# USB_Hub.net
KiCad netlist of a schematic drawn in Altium Designer
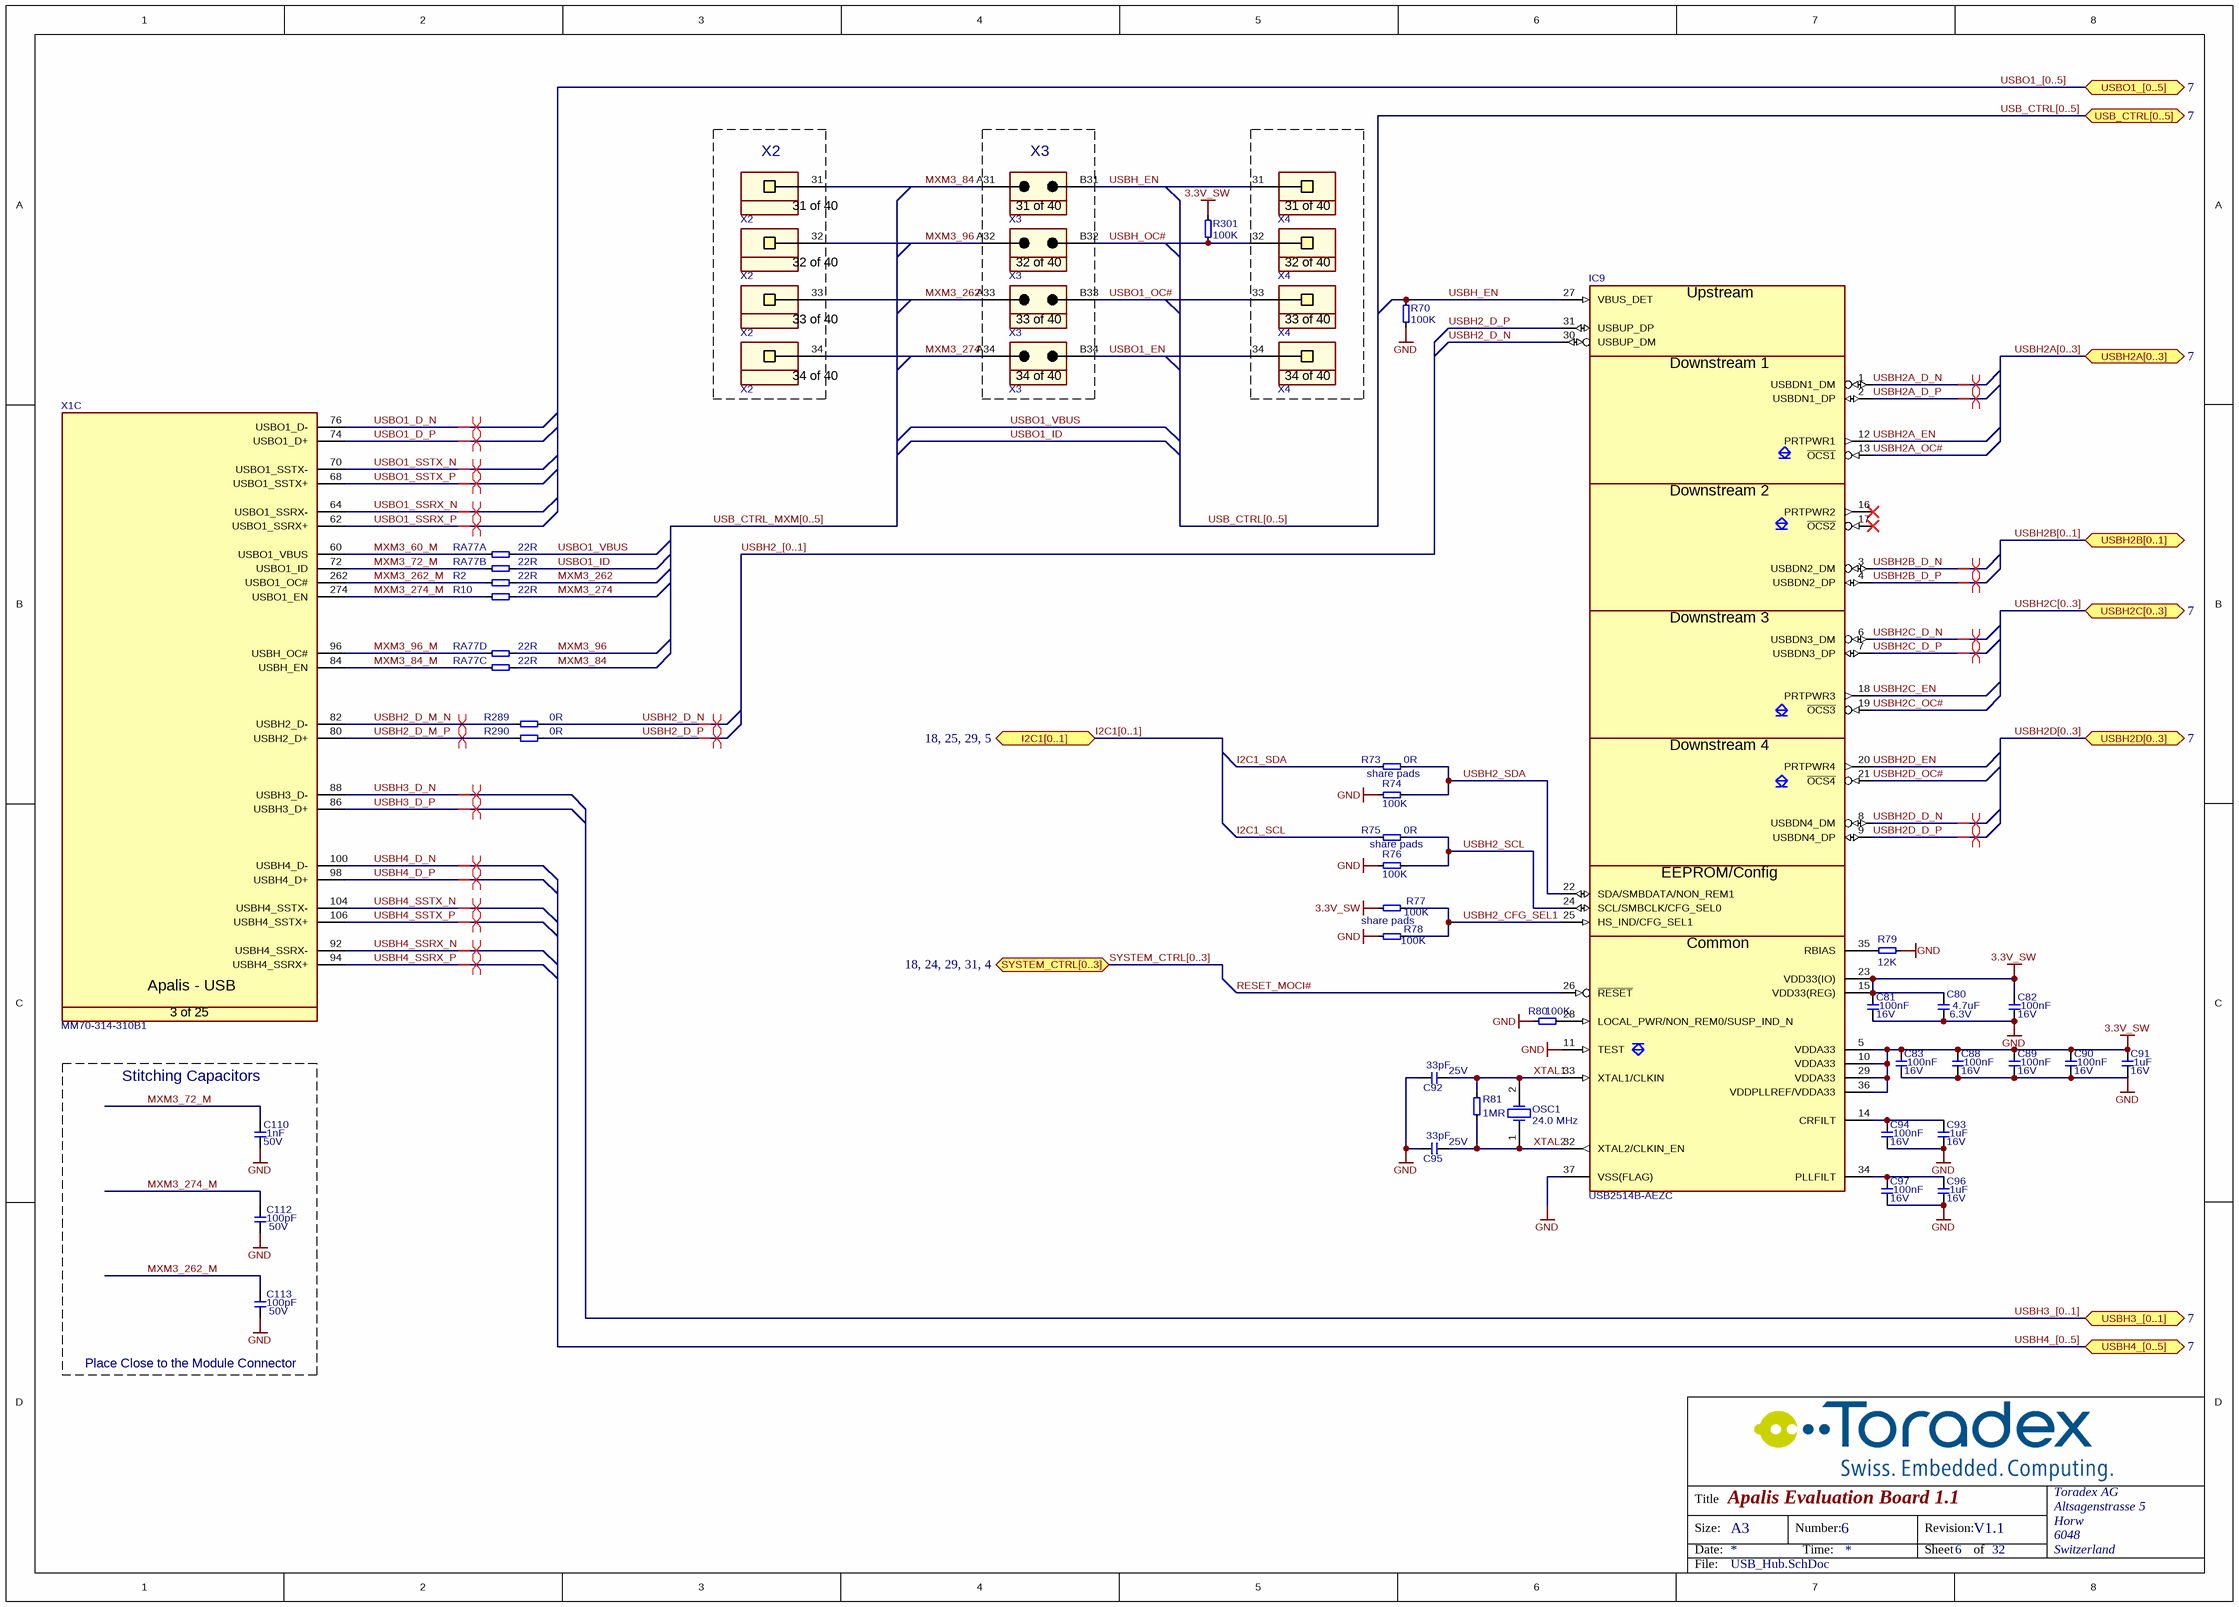
[diagram p0: USB_Hub.SchDoc]

(export (version "E")
  (design (tool "Eeschema 10.0.6"))
  (components
    (comp (ref "C80")
      (value "4.7uF")
      (footprint "T_CAPC0603X33N")
      (description "Capacitor Ceramic X5R 4.7uF 6.3V 20% 0603")
      (fields (field (name "TOLERANCE") "20%") (field (name "RATING") "6.3V"))
      (libsource (lib "Apalis Evaluation Board") (part "C-X5R-4.7uF-6.3V-20%-0603"))
    )
    (comp (ref "C81")
      (value "100nF")
      (footprint "T_CAPC0603X33N")
      (description "Capacitor Ceramic X7R 100nF 16V 10% 0603")
      (fields (field (name "TOLERANCE") "10%") (field (name "RATING") "16V"))
      (libsource (lib "Apalis Evaluation Board") (part "C-X7R-100nF-16V-10%-0603"))
    )
    (comp (ref "C82")
      (value "100nF")
      (footprint "T_CAPC0603X33N")
      (description "Capacitor Ceramic X7R 100nF 16V 10% 0603")
      (fields (field (name "TOLERANCE") "10%") (field (name "RATING") "16V"))
      (libsource (lib "Apalis Evaluation Board") (part "C-X7R-100nF-16V-10%-0603"))
    )
    (comp (ref "C83")
      (value "100nF")
      (footprint "T_CAPC0603X33N")
      (description "Capacitor Ceramic X7R 100nF 16V 10% 0603")
      (fields (field (name "TOLERANCE") "10%") (field (name "RATING") "16V"))
      (libsource (lib "Apalis Evaluation Board") (part "C-X7R-100nF-16V-10%-0603"))
    )
    (comp (ref "C88")
      (value "100nF")
      (footprint "T_CAPC0603X33N")
      (description "Capacitor Ceramic X7R 100nF 16V 10% 0603")
      (fields (field (name "TOLERANCE") "10%") (field (name "RATING") "16V"))
      (libsource (lib "Apalis Evaluation Board") (part "C-X7R-100nF-16V-10%-0603"))
    )
    (comp (ref "C89")
      (value "100nF")
      (footprint "T_CAPC0603X33N")
      (description "Capacitor Ceramic X7R 100nF 16V 10% 0603")
      (fields (field (name "TOLERANCE") "10%") (field (name "RATING") "16V"))
      (libsource (lib "Apalis Evaluation Board") (part "C-X7R-100nF-16V-10%-0603"))
    )
    (comp (ref "C90")
      (value "100nF")
      (footprint "T_CAPC0603X33N")
      (description "Capacitor Ceramic X7R 100nF 16V 10% 0603")
      (fields (field (name "TOLERANCE") "10%") (field (name "RATING") "16V"))
      (libsource (lib "Apalis Evaluation Board") (part "C-X7R-100nF-16V-10%-0603"))
    )
    (comp (ref "C91")
      (value "1uF")
      (footprint "T_CAPC0603X33N")
      (description "Capacitor Ceramic X5R 1uF 16V 20% 0603")
      (fields (field (name "TOLERANCE") "20%") (field (name "RATING") "16V"))
      (libsource (lib "Apalis Evaluation Board") (part "C-X5R-1uF-16V-20%-0603"))
    )
    (comp (ref "C92")
      (value "33pF")
      (footprint "T_CAPC0603X33N")
      (description "Capacitor Ceramic NP0 33pF 25V 10% 0603")
      (fields (field (name "TOLERANCE") "10%") (field (name "RATING") "25V"))
      (libsource (lib "Apalis Evaluation Board") (part "C-NP0-33pF-25V-10%-0603"))
    )
    (comp (ref "C93")
      (value "1uF")
      (footprint "T_CAPC0603X33N")
      (description "Capacitor Ceramic X5R 1uF 16V 20% 0603")
      (fields (field (name "TOLERANCE") "20%") (field (name "RATING") "16V"))
      (libsource (lib "Apalis Evaluation Board") (part "C-X5R-1uF-16V-20%-0603"))
    )
    (comp (ref "C94")
      (value "100nF")
      (footprint "T_CAPC0603X33N")
      (description "Capacitor Ceramic X7R 100nF 16V 10% 0603")
      (fields (field (name "TOLERANCE") "10%") (field (name "RATING") "16V"))
      (libsource (lib "Apalis Evaluation Board") (part "C-X7R-100nF-16V-10%-0603"))
    )
    (comp (ref "C95")
      (value "33pF")
      (footprint "T_CAPC0603X33N")
      (description "Capacitor Ceramic NP0 33pF 25V 10% 0603")
      (fields (field (name "TOLERANCE") "10%") (field (name "RATING") "25V"))
      (libsource (lib "Apalis Evaluation Board") (part "C-NP0-33pF-25V-10%-0603"))
    )
    (comp (ref "C96")
      (value "1uF")
      (footprint "T_CAPC0603X33N")
      (description "Capacitor Ceramic X5R 1uF 16V 20% 0603")
      (fields (field (name "TOLERANCE") "20%") (field (name "RATING") "16V"))
      (libsource (lib "Apalis Evaluation Board") (part "C-X5R-1uF-16V-20%-0603"))
    )
    (comp (ref "C97")
      (value "100nF")
      (footprint "T_CAPC0603X33N")
      (description "Capacitor Ceramic X7R 100nF 16V 10% 0603")
      (fields (field (name "TOLERANCE") "10%") (field (name "RATING") "16V"))
      (libsource (lib "Apalis Evaluation Board") (part "C-X7R-100nF-16V-10%-0603"))
    )
    (comp (ref "C110")
      (value "1nF")
      (footprint "CAPC1005X60N")
      (description "Capacitor Ceramic X7R 1nF 50V 10% 0402")
      (fields (field (name "TOLERANCE") "10%") (field (name "RATING") "50V"))
      (libsource (lib "Apalis Evaluation Board") (part "C-X7R-1nF-50V-10%-0402"))
    )
    (comp (ref "C112")
      (value "100pF")
      (footprint "CAPC1005X60N")
      (description "Capacitor Ceramic X7R 100pF 50V 10% 0402")
      (fields (field (name "TOLERANCE") "10%") (field (name "RATING") "50V"))
      (libsource (lib "Apalis Evaluation Board") (part "C-X7R-100pF-50V-10%-0402"))
    )
    (comp (ref "C113")
      (value "100pF")
      (footprint "CAPC1005X60N")
      (description "Capacitor Ceramic X7R 100pF 50V 10% 0402")
      (fields (field (name "TOLERANCE") "10%") (field (name "RATING") "50V"))
      (libsource (lib "Apalis Evaluation Board") (part "C-X7R-100pF-50V-10%-0402"))
    )
    (comp (ref "IC9")
      (value "USB2514B")
      (footprint "T_SMSC_USB2514B-AEZC")
      (description "4 Port USB HUB")
      (fields (field (name "MANUFACTURER PART NO.") "USB2514B-AEZC"))
      (libsource (lib "Apalis Evaluation Board") (part "IC-SMSC-USB2514B-AEZC"))
    )
    (comp (ref "OSC1")
      (value "24.0 MHz")
      (footprint "T_HORIZON-HEX24")
      (description "Quartz 24.0 MHz")
      (fields
        (field (name "TOLERANCE") "30ppm")
        (field (name "MANUFACTURER PART NO.") "HEX24-24000MHz-18-50R-F-H2-T2-W2-T")
      )
      (libsource (lib "Apalis Evaluation Board") (part "OSC-HORIZON-HEX24-24000MHz-18-50R-F-H2-T2-W2-T"))
    )
    (comp (ref "R2")
      (value "22R")
      (footprint "RESC1005X40N")
      (description "Resistor 22 ohm 63mW 5% 0402")
      (fields (field (name "TOLERANCE") "5%"))
      (libsource (lib "Apalis Evaluation Board") (part "R-22R-63mW-5%-0402"))
    )
    (comp (ref "R10")
      (value "22R")
      (footprint "RESC1005X40N")
      (description "Resistor 22 ohm 63mW 5% 0402")
      (fields (field (name "TOLERANCE") "5%"))
      (libsource (lib "Apalis Evaluation Board") (part "R-22R-63mW-5%-0402"))
    )
    (comp (ref "R70")
      (value "100K")
      (footprint "T_RESC0603X30N")
      (description "Resistor 100 Kohm 63mW 5% 0603")
      (fields (field (name "TOLERANCE") "5%"))
      (libsource (lib "Apalis Evaluation Board") (part "R-100KR-63mW-5%-0603"))
    )
    (comp (ref "R73")
      (value "0R")
      (footprint "T_RESC0603X30N")
      (description "Resistor 0 ohm 63mW 1% 0603")
      (fields (field (name "TOLERANCE") "1%"))
      (libsource (lib "Apalis Evaluation Board") (part "R-0R-63mW-1%-0603"))
    )
    (comp (ref "R74")
      (value "100K")
      (footprint "T_RESC0603X30N")
      (description "Resistor 100 Kohm 63mW 5% 0603")
      (fields (field (name "TOLERANCE") "5%"))
      (libsource (lib "Apalis Evaluation Board") (part "R-100KR-63mW-5%-0603"))
    )
    (comp (ref "R75")
      (value "0R")
      (footprint "T_RESC0603X30N")
      (description "Resistor 0 ohm 63mW 1% 0603")
      (fields (field (name "TOLERANCE") "1%"))
      (libsource (lib "Apalis Evaluation Board") (part "R-0R-63mW-1%-0603"))
    )
    (comp (ref "R76")
      (value "100K")
      (footprint "T_RESC0603X30N")
      (description "Resistor 100 Kohm 63mW 5% 0603")
      (fields (field (name "TOLERANCE") "5%"))
      (libsource (lib "Apalis Evaluation Board") (part "R-100KR-63mW-5%-0603"))
    )
    (comp (ref "R77")
      (value "100K")
      (footprint "T_RESC0603X30N")
      (description "Resistor 100 Kohm 63mW 5% 0603")
      (fields (field (name "TOLERANCE") "5%"))
      (libsource (lib "Apalis Evaluation Board") (part "R-100KR-63mW-5%-0603"))
    )
    (comp (ref "R78")
      (value "100K")
      (footprint "T_RESC0603X30N")
      (description "Resistor 100 Kohm 63mW 5% 0603")
      (fields (field (name "TOLERANCE") "5%"))
      (libsource (lib "Apalis Evaluation Board") (part "R-100KR-63mW-5%-0603"))
    )
    (comp (ref "R79")
      (value "12K")
      (footprint "T_RESC0603X30N")
      (description "Resistor 12 Kohm 63mW 1% 0603")
      (fields (field (name "TOLERANCE") "1%"))
      (libsource (lib "Apalis Evaluation Board") (part "R-12KR-63mW-1%-0603"))
    )
    (comp (ref "R80")
      (value "100K")
      (footprint "T_RESC0603X30N")
      (description "Resistor 100 Kohm 63mW 5% 0603")
      (fields (field (name "TOLERANCE") "5%"))
      (libsource (lib "Apalis Evaluation Board") (part "R-100KR-63mW-5%-0603"))
    )
    (comp (ref "R81")
      (value "1MR")
      (footprint "T_RESC0603X30N")
      (description "Resistor 1Mohm 63mW 5% 0603")
      (fields (field (name "TOLERANCE") "5%"))
      (libsource (lib "Apalis Evaluation Board") (part "R-1MR-63mW-5%-0603"))
    )
    (comp (ref "R289")
      (value "0R")
      (footprint "RESC1005X40N")
      (description "Resistor 0 ohm 63mW 1% 0402")
      (fields (field (name "TOLERANCE") "1%"))
      (libsource (lib "Apalis Evaluation Board") (part "R-0R-63mW-1%-0402"))
    )
    (comp (ref "R290")
      (value "0R")
      (footprint "RESC1005X40N")
      (description "Resistor 0 ohm 63mW 1% 0402")
      (fields (field (name "TOLERANCE") "1%"))
      (libsource (lib "Apalis Evaluation Board") (part "R-0R-63mW-1%-0402"))
    )
    (comp (ref "R301")
      (value "100K")
      (footprint "T_RESC0603X30N")
      (description "Resistor 100 Kohm 63mW 5% 0603")
      (fields (field (name "TOLERANCE") "5%"))
      (libsource (lib "Apalis Evaluation Board") (part "R-100KR-63mW-5%-0603"))
    )
    (comp (ref "RA77")
      (value "22R")
      (footprint "T_Resistor_Array_X4")
      (description "Resistor Array 22 R 63mW 5% 1206")
      (fields (field (name "TOLERANCE") "5%"))
      (libsource (lib "Apalis Evaluation Board") (part "RA-22R-63mW-5%-1206-div"))
    )
    (comp (ref "X1")
      (value "CON-JAE-MM70-314-310B1-314-0.5mm")
      (footprint "T_JAE_MM70-314-310B1")
      (description "MXM3 Connector")
      (fields (field (name "MANUFACTURER PART NO.") "MM70-314-310B1"))
      (libsource (lib "Apalis Evaluation Board") (part "CON-JAE-MM70-314-310B1-314-0.5mm"))
    )
    (comp (ref "X2")
      (value "SSW-110-01-G-S")
      (footprint "T_Samtec_SSW-110-01-G-S")
      (description "Receptacle Female Socket 1x40 pin 2.54mm pitch")
      (libsource (lib "Apalis Evaluation Board") (part "CON-Samtec-SSW-110-01-G-S"))
    )
    (comp (ref "X3")
      (value "TSW-110-07-G-D")
      (footprint "T_Samtec_TSW-110-07-G-D")
      (description "Header 2x40 pin 2.54mm pitch")
      (libsource (lib "Apalis Evaluation Board") (part "CON-Samtec-TSW-110-07-G-D"))
    )
    (comp (ref "X4")
      (value "SSW-110-01-G-S")
      (footprint "T_Samtec_SSW-110-01-G-S")
      (description "Receptacle Female Socket 1x40 pin 2.54mm pitch")
      (libsource (lib "") (part "CON-Samtec-SSW-110-01-G-S_2"))
    )
  )
  (nets
    (net (code "50") (name "/I2C1_SCL") (class "Default")
      (node (ref "R75") (pin "1") (pinfunction "1_1") (pintype "passive"))
    )
    (net (code "51") (name "/I2C1_SDA") (class "Default")
      (node (ref "R73") (pin "1") (pinfunction "1_1") (pintype "passive"))
    )
    (net (code "52") (name "/MXM3_60_M") (class "Default")
      (node (ref "RA77") (pin "1") (pinfunction "1_1") (pintype "passive"))
      (node (ref "X1") (pin "60") (pinfunction "USBO1_VBUS_60") (pintype "passive"))
    )
    (net (code "53") (name "/MXM3_72_M") (class "Default")
      (node (ref "C110") (pin "2") (pinfunction "2_2") (pintype "passive"))
      (node (ref "RA77") (pin "2") (pinfunction "2_2") (pintype "passive"))
      (node (ref "X1") (pin "72") (pinfunction "USBO1_ID_72") (pintype "passive"))
    )
    (net (code "54") (name "/MXM3_84") (class "Default")
      (node (ref "RA77") (pin "7") (pinfunction "7_7") (pintype "passive"))
      (node (ref "X2") (pin "31") (pinfunction "31_31") (pintype "passive"))
      (node (ref "X3") (pin "A31") (pinfunction "A31_A31") (pintype "passive"))
    )
    (net (code "55") (name "/MXM3_84_M") (class "Default")
      (node (ref "RA77") (pin "3") (pinfunction "3_3") (pintype "passive"))
      (node (ref "X1") (pin "84") (pinfunction "USBH_EN_84") (pintype "passive"))
    )
    (net (code "56") (name "/MXM3_96") (class "Default")
      (node (ref "RA77") (pin "8") (pinfunction "8_8") (pintype "passive"))
      (node (ref "X2") (pin "32") (pinfunction "32_32") (pintype "passive"))
      (node (ref "X3") (pin "A32") (pinfunction "A32_A32") (pintype "passive"))
    )
    (net (code "57") (name "/MXM3_96_M") (class "Default")
      (node (ref "RA77") (pin "4") (pinfunction "4_4") (pintype "passive"))
      (node (ref "X1") (pin "96") (pinfunction "USBH_OC#_96") (pintype "passive"))
    )
    (net (code "58") (name "/MXM3_262") (class "Default")
      (node (ref "R2") (pin "2") (pinfunction "2_2") (pintype "passive"))
      (node (ref "X2") (pin "33") (pinfunction "33_33") (pintype "passive"))
      (node (ref "X3") (pin "A33") (pinfunction "A33_A33") (pintype "passive"))
    )
    (net (code "59") (name "/MXM3_262_M") (class "Default")
      (node (ref "C113") (pin "2") (pinfunction "2_2") (pintype "passive"))
      (node (ref "R2") (pin "1") (pinfunction "1_1") (pintype "passive"))
      (node (ref "X1") (pin "262") (pinfunction "USBO1_OC#_262") (pintype "passive"))
    )
    (net (code "60") (name "/MXM3_274") (class "Default")
      (node (ref "R10") (pin "2") (pinfunction "2_2") (pintype "passive"))
      (node (ref "X2") (pin "34") (pinfunction "34_34") (pintype "passive"))
      (node (ref "X3") (pin "A34") (pinfunction "A34_A34") (pintype "passive"))
    )
    (net (code "61") (name "/MXM3_274_M") (class "Default")
      (node (ref "C112") (pin "2") (pinfunction "2_2") (pintype "passive"))
      (node (ref "R10") (pin "1") (pinfunction "1_1") (pintype "passive"))
      (node (ref "X1") (pin "274") (pinfunction "USBO1_EN_274") (pintype "passive"))
    )
    (net (code "62") (name "/RESET_MOCI#") (class "Default")
      (node (ref "IC9") (pin "26") (pinfunction "~{RESET}_26") (pintype "input"))
    )
    (net (code "65") (name "/USBH2A_D_N") (class "Default")
      (node (ref "IC9") (pin "1") (pinfunction "USBDN1_DM_1") (pintype "bidirectional"))
    )
    (net (code "66") (name "/USBH2A_D_P") (class "Default")
      (node (ref "IC9") (pin "2") (pinfunction "USBDN1_DP_2") (pintype "bidirectional"))
    )
    (net (code "67") (name "/USBH2A_EN") (class "Default")
      (node (ref "IC9") (pin "12") (pinfunction "PRTPWR1_12") (pintype "output"))
    )
    (net (code "68") (name "/USBH2A_OC#") (class "Default")
      (node (ref "IC9") (pin "13") (pinfunction "~{OCS1}_13") (pintype "input"))
    )
    (net (code "70") (name "/USBH2B_D_N") (class "Default")
      (node (ref "IC9") (pin "3") (pinfunction "USBDN2_DM_3") (pintype "bidirectional"))
    )
    (net (code "71") (name "/USBH2B_D_P") (class "Default")
      (node (ref "IC9") (pin "4") (pinfunction "USBDN2_DP_4") (pintype "bidirectional"))
    )
    (net (code "73") (name "/USBH2C_D_N") (class "Default")
      (node (ref "IC9") (pin "6") (pinfunction "USBDN3_DM_6") (pintype "bidirectional"))
    )
    (net (code "74") (name "/USBH2C_D_P") (class "Default")
      (node (ref "IC9") (pin "7") (pinfunction "USBDN3_DP_7") (pintype "bidirectional"))
    )
    (net (code "75") (name "/USBH2C_EN") (class "Default")
      (node (ref "IC9") (pin "18") (pinfunction "PRTPWR3_18") (pintype "output"))
    )
    (net (code "76") (name "/USBH2C_OC#") (class "Default")
      (node (ref "IC9") (pin "19") (pinfunction "~{OCS3}_19") (pintype "input"))
    )
    (net (code "78") (name "/USBH2D_D_N") (class "Default")
      (node (ref "IC9") (pin "8") (pinfunction "USBDN4_DM_8") (pintype "bidirectional"))
    )
    (net (code "79") (name "/USBH2D_D_P") (class "Default")
      (node (ref "IC9") (pin "9") (pinfunction "USBDN4_DP_9") (pintype "bidirectional"))
    )
    (net (code "80") (name "/USBH2D_EN") (class "Default")
      (node (ref "IC9") (pin "20") (pinfunction "PRTPWR4_20") (pintype "output"))
    )
    (net (code "81") (name "/USBH2D_OC#") (class "Default")
      (node (ref "IC9") (pin "21") (pinfunction "~{OCS4}_21") (pintype "input"))
    )
    (net (code "82") (name "/USBH2_CFG_SEL1") (class "Default")
      (node (ref "IC9") (pin "25") (pinfunction "HS_IND/CFG_SEL1_25") (pintype "input"))
      (node (ref "R77") (pin "1") (pinfunction "1_1") (pintype "passive"))
      (node (ref "R78") (pin "1") (pinfunction "1_1") (pintype "passive"))
    )
    (net (code "83") (name "/USBH2_D_M_N") (class "Default")
      (node (ref "R289") (pin "1") (pinfunction "1_1") (pintype "passive"))
      (node (ref "X1") (pin "82") (pinfunction "USBH2_D-_82") (pintype "passive"))
    )
    (net (code "84") (name "/USBH2_D_M_P") (class "Default")
      (node (ref "R290") (pin "1") (pinfunction "1_1") (pintype "passive"))
      (node (ref "X1") (pin "80") (pinfunction "USBH2_D+_80") (pintype "passive"))
    )
    (net (code "85") (name "/USBH2_D_N") (class "Default")
      (node (ref "IC9") (pin "30") (pinfunction "USBUP_DM_30") (pintype "bidirectional"))
      (node (ref "R289") (pin "2") (pinfunction "2_2") (pintype "passive"))
    )
    (net (code "86") (name "/USBH2_D_P") (class "Default")
      (node (ref "IC9") (pin "31") (pinfunction "USBUP_DP_31") (pintype "bidirectional"))
      (node (ref "R290") (pin "2") (pinfunction "2_2") (pintype "passive"))
    )
    (net (code "87") (name "/USBH2_SCL") (class "Default")
      (node (ref "IC9") (pin "24") (pinfunction "SCL/SMBCLK/CFG_SEL0_24") (pintype "bidirectional"))
      (node (ref "R75") (pin "2") (pinfunction "2_2") (pintype "passive"))
      (node (ref "R76") (pin "1") (pinfunction "1_1") (pintype "passive"))
    )
    (net (code "88") (name "/USBH2_SDA") (class "Default")
      (node (ref "IC9") (pin "22") (pinfunction "SDA/SMBDATA/NON_REM1_22") (pintype "bidirectional"))
      (node (ref "R73") (pin "2") (pinfunction "2_2") (pintype "passive"))
      (node (ref "R74") (pin "1") (pinfunction "1_1") (pintype "passive"))
    )
    (net (code "90") (name "/USBH3_D_N") (class "Default")
      (node (ref "X1") (pin "88") (pinfunction "USBH3_D-_88") (pintype "passive"))
    )
    (net (code "91") (name "/USBH3_D_P") (class "Default")
      (node (ref "X1") (pin "86") (pinfunction "USBH3_D+_86") (pintype "passive"))
    )
    (net (code "93") (name "/USBH4_D_N") (class "Default")
      (node (ref "X1") (pin "100") (pinfunction "USBH4_D-_100") (pintype "passive"))
    )
    (net (code "94") (name "/USBH4_D_P") (class "Default")
      (node (ref "X1") (pin "98") (pinfunction "USBH4_D+_98") (pintype "passive"))
    )
    (net (code "95") (name "/USBH4_SSRX_N") (class "Default")
      (node (ref "X1") (pin "92") (pinfunction "USBH4_SSRX-_92") (pintype "passive"))
    )
    (net (code "96") (name "/USBH4_SSRX_P") (class "Default")
      (node (ref "X1") (pin "94") (pinfunction "USBH4_SSRX+_94") (pintype "passive"))
    )
    (net (code "97") (name "/USBH4_SSTX_N") (class "Default")
      (node (ref "X1") (pin "104") (pinfunction "USBH4_SSTX-_104") (pintype "passive"))
    )
    (net (code "98") (name "/USBH4_SSTX_P") (class "Default")
      (node (ref "X1") (pin "106") (pinfunction "USBH4_SSTX+_106") (pintype "passive"))
    )
    (net (code "100") (name "/USBH_EN") (class "Default")
      (node (ref "IC9") (pin "27") (pinfunction "VBUS_DET_27") (pintype "input"))
      (node (ref "R70") (pin "2") (pinfunction "2_2") (pintype "passive"))
      (node (ref "X3") (pin "B31") (pinfunction "B31_B31") (pintype "passive"))
      (node (ref "X4") (pin "31") (pinfunction "31_31") (pintype "passive"))
    )
    (net (code "101") (name "/USBH_OC#") (class "Default")
      (node (ref "R301") (pin "2") (pinfunction "2_2") (pintype "passive"))
      (node (ref "X3") (pin "B32") (pinfunction "B32_B32") (pintype "passive"))
      (node (ref "X4") (pin "32") (pinfunction "32_32") (pintype "passive"))
    )
    (net (code "102") (name "/USBO1_D_N") (class "Default")
      (node (ref "X1") (pin "76") (pinfunction "USBO1_D-_76") (pintype "passive"))
    )
    (net (code "103") (name "/USBO1_D_P") (class "Default")
      (node (ref "X1") (pin "74") (pinfunction "USBO1_D+_74") (pintype "passive"))
    )
    (net (code "104") (name "/USBO1_EN") (class "Default")
      (node (ref "X3") (pin "B34") (pinfunction "B34_B34") (pintype "passive"))
      (node (ref "X4") (pin "34") (pinfunction "34_34") (pintype "passive"))
    )
    (net (code "105") (name "/USBO1_ID") (class "Default")
      (node (ref "RA77") (pin "6") (pinfunction "6_6") (pintype "passive"))
    )
    (net (code "106") (name "/USBO1_OC#") (class "Default")
      (node (ref "X3") (pin "B33") (pinfunction "B33_B33") (pintype "passive"))
      (node (ref "X4") (pin "33") (pinfunction "33_33") (pintype "passive"))
    )
    (net (code "107") (name "/USBO1_SSRX_N") (class "Default")
      (node (ref "X1") (pin "64") (pinfunction "USBO1_SSRX-_64") (pintype "passive"))
    )
    (net (code "108") (name "/USBO1_SSRX_P") (class "Default")
      (node (ref "X1") (pin "62") (pinfunction "USBO1_SSRX+_62") (pintype "passive"))
    )
    (net (code "109") (name "/USBO1_SSTX_N") (class "Default")
      (node (ref "X1") (pin "70") (pinfunction "USBO1_SSTX-_70") (pintype "passive"))
    )
    (net (code "110") (name "/USBO1_SSTX_P") (class "Default")
      (node (ref "X1") (pin "68") (pinfunction "USBO1_SSTX+_68") (pintype "passive"))
    )
    (net (code "111") (name "/USBO1_VBUS") (class "Default")
      (node (ref "RA77") (pin "5") (pinfunction "5_5") (pintype "passive"))
    )
    (net (code "115") (name "/XTAL1") (class "Default")
      (node (ref "C92") (pin "2") (pinfunction "2_2") (pintype "passive"))
      (node (ref "IC9") (pin "33") (pinfunction "XTAL1/CLKIN_33") (pintype "input"))
      (node (ref "OSC1") (pin "2") (pinfunction "OSC2_2") (pintype "passive"))
      (node (ref "R81") (pin "2") (pinfunction "2_2") (pintype "passive"))
    )
    (net (code "116") (name "/XTAL2") (class "Default")
      (node (ref "C95") (pin "2") (pinfunction "2_2") (pintype "passive"))
      (node (ref "IC9") (pin "32") (pinfunction "XTAL2/CLKIN_EN_32") (pintype "output"))
      (node (ref "OSC1") (pin "1") (pinfunction "OSC1_1") (pintype "passive"))
      (node (ref "R81") (pin "1") (pinfunction "1_1") (pintype "passive"))
    )
    (net (code "117") (name "3.3V_SW") (class "Default")
      (node (ref "C80") (pin "2") (pinfunction "2_2") (pintype "passive"))
      (node (ref "C81") (pin "2") (pinfunction "2_2") (pintype "passive"))
      (node (ref "C82") (pin "2") (pinfunction "2_2") (pintype "passive"))
      (node (ref "C83") (pin "2") (pinfunction "2_2") (pintype "passive"))
      (node (ref "C88") (pin "2") (pinfunction "2_2") (pintype "passive"))
      (node (ref "C89") (pin "2") (pinfunction "2_2") (pintype "passive"))
      (node (ref "C90") (pin "2") (pinfunction "2_2") (pintype "passive"))
      (node (ref "C91") (pin "2") (pinfunction "2_2") (pintype "passive"))
      (node (ref "IC9") (pin "10") (pinfunction "VDDA33_10") (pintype "power_in"))
      (node (ref "IC9") (pin "15") (pinfunction "VDD33(REG)_15") (pintype "power_in"))
      (node (ref "IC9") (pin "23") (pinfunction "VDD33(IO)_23") (pintype "power_in"))
      (node (ref "IC9") (pin "29") (pinfunction "VDDA33_29") (pintype "power_in"))
      (node (ref "IC9") (pin "36") (pinfunction "VDDPLLREF/VDDA33_36") (pintype "power_in"))
      (node (ref "IC9") (pin "5") (pinfunction "VDDA33_5") (pintype "power_in"))
      (node (ref "R301") (pin "1") (pinfunction "1_1") (pintype "passive"))
      (node (ref "R77") (pin "2") (pinfunction "2_2") (pintype "passive"))
    )
    (net (code "118") (name "GND") (class "Default")
      (node (ref "C110") (pin "1") (pinfunction "1_1") (pintype "passive"))
      (node (ref "C112") (pin "1") (pinfunction "1_1") (pintype "passive"))
      (node (ref "C113") (pin "1") (pinfunction "1_1") (pintype "passive"))
      (node (ref "C80") (pin "1") (pinfunction "1_1") (pintype "passive"))
      (node (ref "C81") (pin "1") (pinfunction "1_1") (pintype "passive"))
      (node (ref "C82") (pin "1") (pinfunction "1_1") (pintype "passive"))
      (node (ref "C83") (pin "1") (pinfunction "1_1") (pintype "passive"))
      (node (ref "C88") (pin "1") (pinfunction "1_1") (pintype "passive"))
      (node (ref "C89") (pin "1") (pinfunction "1_1") (pintype "passive"))
      (node (ref "C90") (pin "1") (pinfunction "1_1") (pintype "passive"))
      (node (ref "C91") (pin "1") (pinfunction "1_1") (pintype "passive"))
      (node (ref "C92") (pin "1") (pinfunction "1_1") (pintype "passive"))
      (node (ref "C93") (pin "1") (pinfunction "1_1") (pintype "passive"))
      (node (ref "C94") (pin "1") (pinfunction "1_1") (pintype "passive"))
      (node (ref "C95") (pin "1") (pinfunction "1_1") (pintype "passive"))
      (node (ref "C96") (pin "1") (pinfunction "1_1") (pintype "passive"))
      (node (ref "C97") (pin "1") (pinfunction "1_1") (pintype "passive"))
      (node (ref "IC9") (pin "11") (pinfunction "TEST_11") (pintype "input"))
      (node (ref "IC9") (pin "37") (pinfunction "VSS(FLAG)_37") (pintype "power_in"))
      (node (ref "R70") (pin "1") (pinfunction "1_1") (pintype "passive"))
      (node (ref "R74") (pin "2") (pinfunction "2_2") (pintype "passive"))
      (node (ref "R76") (pin "2") (pinfunction "2_2") (pintype "passive"))
      (node (ref "R78") (pin "2") (pinfunction "2_2") (pintype "passive"))
      (node (ref "R79") (pin "1") (pinfunction "1_1") (pintype "passive"))
      (node (ref "R80") (pin "1") (pinfunction "1_1") (pintype "passive"))
    )
    (net (code "119") (name "Net-(IC9-CRFILT)") (class "Default")
      (node (ref "C93") (pin "2") (pinfunction "2_2") (pintype "passive"))
      (node (ref "C94") (pin "2") (pinfunction "2_2") (pintype "passive"))
      (node (ref "IC9") (pin "14") (pinfunction "CRFILT_14") (pintype "power_in"))
    )
    (net (code "120") (name "Net-(IC9-LOCAL_PWR{slash}NON_REM0{slash}SUSP_IND_N)") (class "Default")
      (node (ref "IC9") (pin "28") (pinfunction "LOCAL_PWR/NON_REM0/SUSP_IND_N_28") (pintype "input"))
      (node (ref "R80") (pin "2") (pinfunction "2_2") (pintype "passive"))
    )
    (net (code "121") (name "Net-(IC9-PLLFILT)") (class "Default")
      (node (ref "C96") (pin "2") (pinfunction "2_2") (pintype "passive"))
      (node (ref "C97") (pin "2") (pinfunction "2_2") (pintype "passive"))
      (node (ref "IC9") (pin "34") (pinfunction "PLLFILT_34") (pintype "power_in"))
    )
    (net (code "122") (name "Net-(IC9-RBIAS)") (class "Default")
      (node (ref "IC9") (pin "35") (pinfunction "RBIAS_35") (pintype "passive"))
      (node (ref "R79") (pin "2") (pinfunction "2_2") (pintype "passive"))
    )
    (net (code "123") (name "unconnected-(IC9-PRTPWR2-Pad16)") (class "Default")
      (node (ref "IC9") (pin "16") (pinfunction "PRTPWR2_16") (pintype "output+no_connect"))
    )
    (net (code "124") (name "unconnected-(IC9-~{OCS2}-Pad17)") (class "Default")
      (node (ref "IC9") (pin "17") (pinfunction "~{OCS2}_17") (pintype "input+no_connect"))
    )
  )
)
